# SH1_-_CAN.net
KiCad netlist of a schematic drawn in Altium Designer
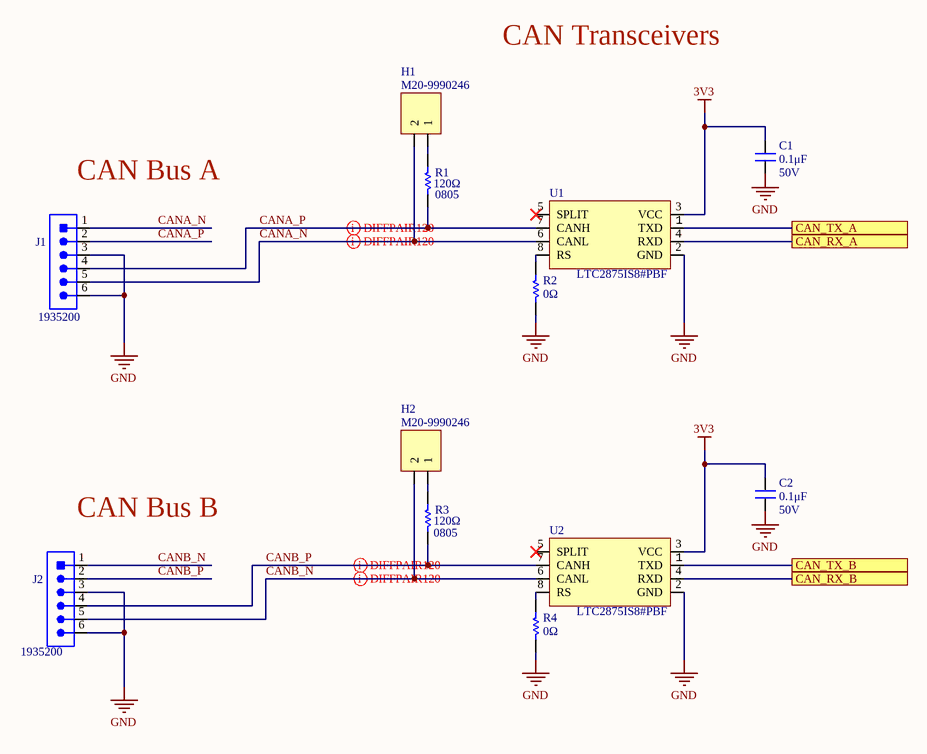
[diagram p0: SH1 - CAN.SchDoc]

(export (version "E")
  (design (tool "Eeschema 10.0.6"))
  (components
    (comp (ref "C1")
      (value "0.1μF")
      (footprint "CAP2012")
      (description "CAP CER 0.1UF 50V X7R 0805")
      (fields
        (field (name "VOLTAGE RATING") "50V")
        (field (name "LCSC PART #") "C49678")
        (field (name "Comment") "CAP_0.1uF_50V_0805")
      )
      (libsource (lib "UWRT_Schematic_Library_2020") (part "CAP_0.1uF_50V_0805"))
    )
    (comp (ref "C2")
      (value "0.1μF")
      (footprint "CAP2012")
      (description "CAP CER 0.1UF 50V X7R 0805")
      (fields
        (field (name "VOLTAGE RATING") "50V")
        (field (name "LCSC PART #") "C49678")
        (field (name "Comment") "CAP_0.1uF_50V_0805")
      )
      (libsource (lib "UWRT_Schematic_Library_2020") (part "CAP_0.1uF_50V_0805"))
    )
    (comp (ref "H1")
      (value "JUMPER")
      (footprint "HDR1X2")
      (description "HEADER 2X1")
      (fields (field (name "MANUFACTURER PART NUMBER 1") "M20-9990246"))
      (libsource (lib "UWRT_Schematic_Library_2020") (part "JUMPER"))
    )
    (comp (ref "H2")
      (value "JUMPER")
      (footprint "HDR1X2")
      (description "HEADER 2X1")
      (fields (field (name "MANUFACTURER PART NUMBER 1") "M20-9990246"))
      (libsource (lib "UWRT_Schematic_Library_2020") (part "JUMPER"))
    )
    (comp (ref "J1")
      (value "CON_6POS_SCREW_TERM")
      (footprint "1935200")
      (description "TERM BLK 6POS SIDE ENTRY 5MM")
      (fields (field (name "MANUFACTURER PART NUMBER 1") "1935200"))
      (libsource (lib "UWRT_Schematic_Library_2020") (part "CON_6POS_SCREW_TERM"))
    )
    (comp (ref "J2")
      (value "CON_6POS_SCREW_TERM")
      (footprint "1935200")
      (description "TERM BLK 6POS SIDE ENTRY 5MM")
      (fields (field (name "MANUFACTURER PART NUMBER 1") "1935200"))
      (libsource (lib "UWRT_Schematic_Library_2020") (part "CON_6POS_SCREW_TERM"))
    )
    (comp (ref "R1")
      (value "120Ω")
      (footprint "RESC0805")
      (description "RES 120 OHM 1% 1/8W 0805")
      (fields
        (field (name "LCSC PART #") "C17437")
        (field (name "PACKAGE/FOOTPRINT") "0805")
        (field (name "Comment") "RES_120Ω_0805_1%")
      )
      (libsource (lib "UWRT_Schematic_Library_2020") (part "RES_120Ω_0805_1%"))
    )
    (comp (ref "R2")
      (value "0Ω")
      (footprint "RESC0805")
      (description "RES 0 OHM JUMPER 1/8W 0805")
      (fields (field (name "LCSC PART #") "C17477") (field (name "Comment") "RES_0Ω_0805"))
      (libsource (lib "UWRT_Schematic_Library_2020") (part "RES_0Ω_0805"))
    )
    (comp (ref "R3")
      (value "120Ω")
      (footprint "RESC0805")
      (description "RES 120 OHM 1% 1/8W 0805")
      (fields
        (field (name "LCSC PART #") "C17437")
        (field (name "PACKAGE/FOOTPRINT") "0805")
        (field (name "Comment") "RES_120Ω_0805_1%")
      )
      (libsource (lib "UWRT_Schematic_Library_2020") (part "RES_120Ω_0805_1%"))
    )
    (comp (ref "R4")
      (value "0Ω")
      (footprint "RESC0805")
      (description "RES 0 OHM JUMPER 1/8W 0805")
      (fields (field (name "LCSC PART #") "C17477") (field (name "Comment") "RES_0Ω_0805"))
      (libsource (lib "UWRT_Schematic_Library_2020") (part "RES_0Ω_0805"))
    )
    (comp (ref "U1")
      (value "IC_CAN_TRANSCEIVER")
      (footprint "LT-S8_N")
      (description "IC TXRX CAN 4MBPS 8SO")
      (fields
        (field (name "MANUFACTURER PART NUMBER 1") "LTC2875IS8#PBF")
        (field (name "LCSC PART #") "C117076")
      )
      (libsource (lib "UWRT_Schematic_Library_2020") (part "IC_CAN_TRANSCEIVER"))
    )
    (comp (ref "U2")
      (value "IC_CAN_TRANSCEIVER")
      (footprint "LT-S8_N")
      (description "IC TXRX CAN 4MBPS 8SO")
      (fields
        (field (name "MANUFACTURER PART NUMBER 1") "LTC2875IS8#PBF")
        (field (name "LCSC PART #") "C117076")
      )
      (libsource (lib "UWRT_Schematic_Library_2020") (part "IC_CAN_TRANSCEIVER"))
    )
  )
  (nets
    (net (code "1") (name "/CANA_N") (class "Default")
      (node (ref "H1") (pin "2") (pinfunction "2_2") (pintype "passive"))
      (node (ref "J1") (pin "1") (pinfunction "1_1") (pintype "passive"))
      (node (ref "J1") (pin "5") (pinfunction "5_5") (pintype "passive"))
      (node (ref "U1") (pin "6") (pinfunction "CANL_6") (pintype "passive"))
    )
    (net (code "2") (name "/CANA_P") (class "Default")
      (node (ref "J1") (pin "2") (pinfunction "2_2") (pintype "passive"))
      (node (ref "J1") (pin "4") (pinfunction "4_4") (pintype "passive"))
      (node (ref "R1") (pin "1") (pinfunction "1_1") (pintype "passive"))
      (node (ref "U1") (pin "7") (pinfunction "CANH_7") (pintype "passive"))
    )
    (net (code "3") (name "/CANB_N") (class "Default")
      (node (ref "H2") (pin "2") (pinfunction "2_2") (pintype "passive"))
      (node (ref "J2") (pin "1") (pinfunction "1_1") (pintype "passive"))
      (node (ref "J2") (pin "5") (pinfunction "5_5") (pintype "passive"))
      (node (ref "U2") (pin "6") (pinfunction "CANL_6") (pintype "passive"))
    )
    (net (code "4") (name "/CANB_P") (class "Default")
      (node (ref "J2") (pin "2") (pinfunction "2_2") (pintype "passive"))
      (node (ref "J2") (pin "4") (pinfunction "4_4") (pintype "passive"))
      (node (ref "R3") (pin "1") (pinfunction "1_1") (pintype "passive"))
      (node (ref "U2") (pin "7") (pinfunction "CANH_7") (pintype "passive"))
    )
    (net (code "5") (name "/CAN_RX_A") (class "Default")
      (node (ref "U1") (pin "4") (pinfunction "RXD_4") (pintype "passive"))
    )
    (net (code "6") (name "/CAN_RX_B") (class "Default")
      (node (ref "U2") (pin "4") (pinfunction "RXD_4") (pintype "passive"))
    )
    (net (code "7") (name "/CAN_TX_A") (class "Default")
      (node (ref "U1") (pin "1") (pinfunction "TXD_1") (pintype "passive"))
    )
    (net (code "8") (name "/CAN_TX_B") (class "Default")
      (node (ref "U2") (pin "1") (pinfunction "TXD_1") (pintype "passive"))
    )
    (net (code "9") (name "3V3") (class "Default")
      (node (ref "C1") (pin "1") (pinfunction "1_1") (pintype "passive"))
      (node (ref "C2") (pin "1") (pinfunction "1_1") (pintype "passive"))
      (node (ref "U1") (pin "3") (pinfunction "VCC_3") (pintype "passive"))
      (node (ref "U2") (pin "3") (pinfunction "VCC_3") (pintype "passive"))
    )
    (net (code "10") (name "GND") (class "Default")
      (node (ref "C1") (pin "2") (pinfunction "2_2") (pintype "passive"))
      (node (ref "C2") (pin "2") (pinfunction "2_2") (pintype "passive"))
      (node (ref "J1") (pin "3") (pinfunction "3_3") (pintype "passive"))
      (node (ref "J1") (pin "6") (pinfunction "6_6") (pintype "passive"))
      (node (ref "J2") (pin "3") (pinfunction "3_3") (pintype "passive"))
      (node (ref "J2") (pin "6") (pinfunction "6_6") (pintype "passive"))
      (node (ref "R2") (pin "1") (pinfunction "1_1") (pintype "passive"))
      (node (ref "R4") (pin "1") (pinfunction "1_1") (pintype "passive"))
      (node (ref "U1") (pin "2") (pinfunction "GND_2") (pintype "passive"))
      (node (ref "U2") (pin "2") (pinfunction "GND_2") (pintype "passive"))
    )
    (net (code "11") (name "Net-(H1-Pad1)") (class "Default")
      (node (ref "H1") (pin "1") (pinfunction "1_1") (pintype "passive"))
      (node (ref "R1") (pin "2") (pinfunction "2_2") (pintype "passive"))
    )
    (net (code "12") (name "Net-(H2-Pad1)") (class "Default")
      (node (ref "H2") (pin "1") (pinfunction "1_1") (pintype "passive"))
      (node (ref "R3") (pin "2") (pinfunction "2_2") (pintype "passive"))
    )
    (net (code "13") (name "Net-(U1-RS)") (class "Default")
      (node (ref "R2") (pin "2") (pinfunction "2_2") (pintype "passive"))
      (node (ref "U1") (pin "8") (pinfunction "RS_8") (pintype "passive"))
    )
    (net (code "14") (name "Net-(U2-RS)") (class "Default")
      (node (ref "R4") (pin "2") (pinfunction "2_2") (pintype "passive"))
      (node (ref "U2") (pin "8") (pinfunction "RS_8") (pintype "passive"))
    )
    (net (code "15") (name "unconnected-(U1-SPLIT-Pad5)") (class "Default")
      (node (ref "U1") (pin "5") (pinfunction "SPLIT_5") (pintype "passive+no_connect"))
    )
    (net (code "16") (name "unconnected-(U2-SPLIT-Pad5)") (class "Default")
      (node (ref "U2") (pin "5") (pinfunction "SPLIT_5") (pintype "passive+no_connect"))
    )
  )
)
